# MSP_Power_Board_revA_1.net
KiCad netlist of a schematic drawn in EAGLE
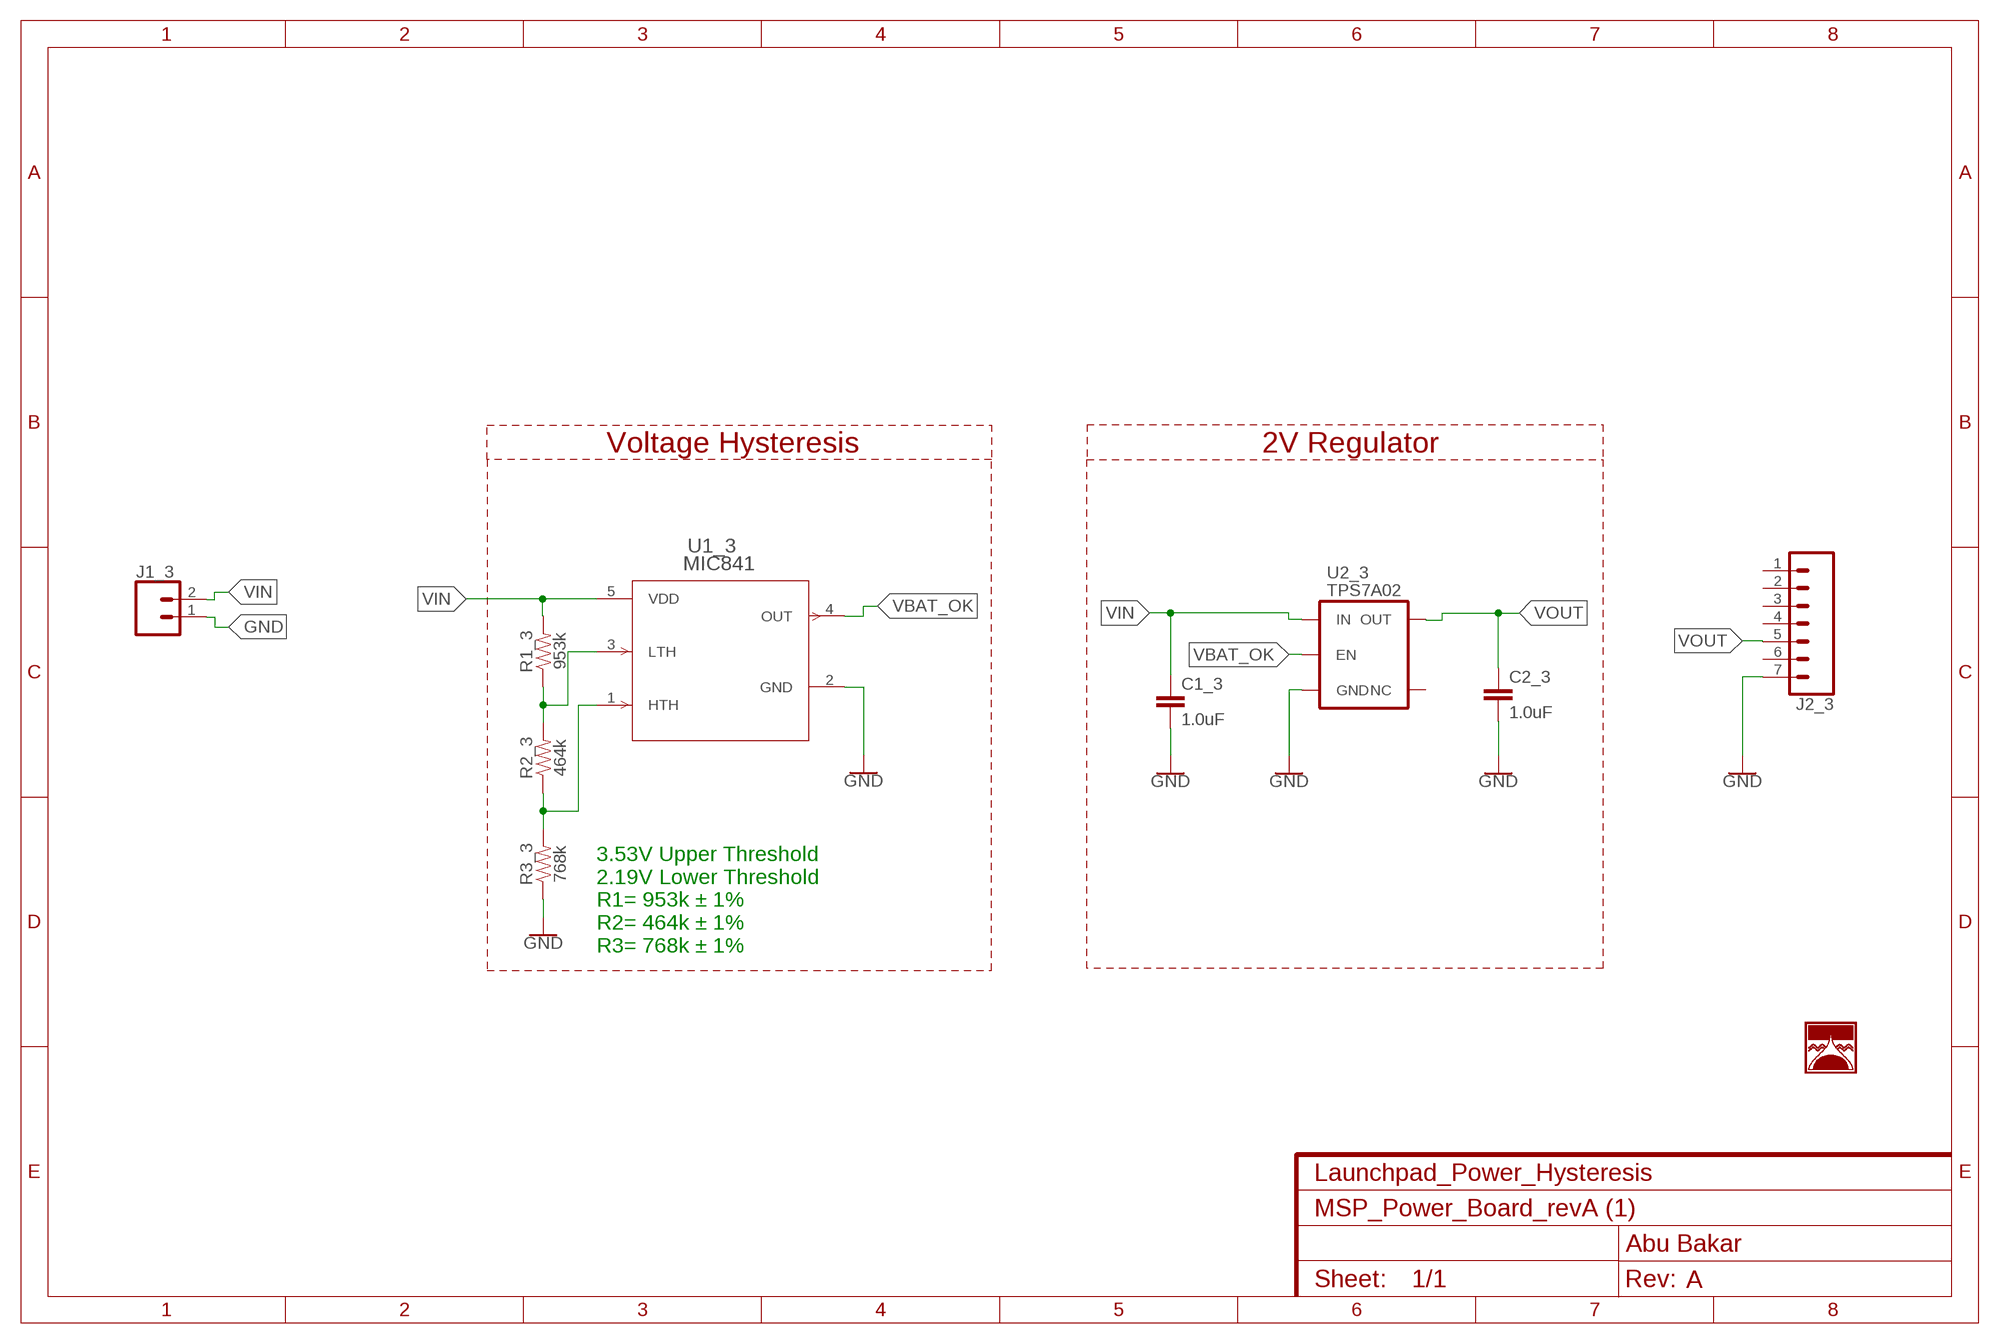
[diagram p0: schematic, sheet 1]

(export (version "E")
  (design (tool "Eeschema 10.0.6"))
  (components
    (comp (ref "C1_3")
      (value "1.0uF")
      (footprint "eagle-import:0603")
      (libsource (lib "eagle-import") (part "1.0UF-0603-16V-10%"))
    )
    (comp (ref "C2_3")
      (value "1.0uF")
      (footprint "eagle-import:0603")
      (libsource (lib "eagle-import") (part "1.0UF-0603-16V-10%"))
    )
    (comp (ref "J1_3")
      (value "CONN_02")
      (footprint "eagle-import:1X02")
      (libsource (lib "eagle-import") (part "CONN_02"))
    )
    (comp (ref "J2_3")
      (value "CONN_07")
      (footprint "eagle-import:1X07")
      (libsource (lib "eagle-import") (part "CONN_07"))
    )
    (comp (ref "R1_3")
      (value "953k")
      (footprint "eagle-import:0603")
      (libsource (lib "eagle-import") (part "RESISTOR0603"))
    )
    (comp (ref "R2_3")
      (value "464k")
      (footprint "eagle-import:0603")
      (libsource (lib "eagle-import") (part "RESISTOR0603"))
    )
    (comp (ref "R3_3")
      (value "768k")
      (footprint "eagle-import:0603")
      (libsource (lib "eagle-import") (part "RESISTOR0603"))
    )
    (comp (ref "U$1_3")
      (value "KAMOAMOA_LOGO_4X4MM")
      (footprint "eagle-import:LOGO_4X4MM")
      (libsource (lib "eagle-import") (part "KAMOAMOA_LOGO_4X4MM"))
    )
    (comp (ref "U1_3")
      (value "MIC841")
      (footprint "eagle-import:SC-70_C5_MCH")
      (fields
        (field (name "MANUFACTURER_PART_NUMBER") "MIC841NYC5-TR")
        (field (name "COPYRIGHT") "Copyright (C) 2018 Accelerated Designs. All rights reserved")
      )
      (libsource (lib "eagle-import") (part "MIC841HYC5-TR"))
    )
    (comp (ref "U2_3")
      (value "TPS7A02")
      (footprint "eagle-import:SOT23-5")
      (libsource (lib "eagle-import") (part "TPS7A02"))
    )
  )
  (nets
    (net (code "1") (name "GND") (class "Default")
      (node (ref "C1_3") (pin "2") (pinfunction "2_2") (pintype "passive"))
      (node (ref "C2_3") (pin "2") (pinfunction "2_2") (pintype "passive"))
      (node (ref "J1_3") (pin "1") (pinfunction "1_1") (pintype "passive"))
      (node (ref "J2_3") (pin "7") (pinfunction "7_7") (pintype "passive"))
      (node (ref "R3_3") (pin "1") (pinfunction "1_1") (pintype "passive"))
      (node (ref "U1_3") (pin "2") (pinfunction "GND_2") (pintype "power_in"))
      (node (ref "U2_3") (pin "2") (pinfunction "GND_2") (pintype "input"))
    )
    (net (code "2") (name "Net-(U1_3-HTH)") (class "Default")
      (node (ref "R2_3") (pin "1") (pinfunction "1_1") (pintype "passive"))
      (node (ref "R3_3") (pin "2") (pinfunction "2_2") (pintype "passive"))
      (node (ref "U1_3") (pin "1") (pinfunction "HTH_1") (pintype "input"))
    )
    (net (code "3") (name "Net-(U1_3-LTH)") (class "Default")
      (node (ref "R1_3") (pin "1") (pinfunction "1_1") (pintype "passive"))
      (node (ref "R2_3") (pin "2") (pinfunction "2_2") (pintype "passive"))
      (node (ref "U1_3") (pin "3") (pinfunction "LTH_3") (pintype "input"))
    )
    (net (code "4") (name "VBAT_OK") (class "Default")
      (node (ref "U1_3") (pin "4") (pinfunction "OUT_4") (pintype "output"))
      (node (ref "U2_3") (pin "3") (pinfunction "EN_3") (pintype "input"))
    )
    (net (code "5") (name "VIN") (class "Default")
      (node (ref "C1_3") (pin "1") (pinfunction "1_1") (pintype "passive"))
      (node (ref "J1_3") (pin "2") (pinfunction "2_2") (pintype "passive"))
      (node (ref "R1_3") (pin "2") (pinfunction "2_2") (pintype "passive"))
      (node (ref "U1_3") (pin "5") (pinfunction "VDD_5") (pintype "power_in"))
      (node (ref "U2_3") (pin "1") (pinfunction "IN_1") (pintype "input"))
    )
    (net (code "6") (name "VOUT") (class "Default")
      (node (ref "C2_3") (pin "1") (pinfunction "1_1") (pintype "passive"))
      (node (ref "J2_3") (pin "5") (pinfunction "5_5") (pintype "passive"))
      (node (ref "U2_3") (pin "5") (pinfunction "OUT_5") (pintype "passive"))
    )
    (net (code "7") (name "unconnected-(J2_3-Pad1)") (class "Default")
      (node (ref "J2_3") (pin "1") (pinfunction "1_1") (pintype "passive"))
    )
    (net (code "8") (name "unconnected-(J2_3-Pad2)") (class "Default")
      (node (ref "J2_3") (pin "2") (pinfunction "2_2") (pintype "passive"))
    )
    (net (code "9") (name "unconnected-(J2_3-Pad3)") (class "Default")
      (node (ref "J2_3") (pin "3") (pinfunction "3_3") (pintype "passive"))
    )
    (net (code "10") (name "unconnected-(J2_3-Pad4)") (class "Default")
      (node (ref "J2_3") (pin "4") (pinfunction "4_4") (pintype "passive"))
    )
    (net (code "11") (name "unconnected-(J2_3-Pad6)") (class "Default")
      (node (ref "J2_3") (pin "6") (pinfunction "6_6") (pintype "passive"))
    )
    (net (code "12") (name "unconnected-(U2_3-NC-Pad4)") (class "Default")
      (node (ref "U2_3") (pin "4") (pinfunction "NC_4") (pintype "no_connect"))
    )
  )
)
